# Sensor-touch.net
KiCad netlist of a schematic drawn in EAGLE
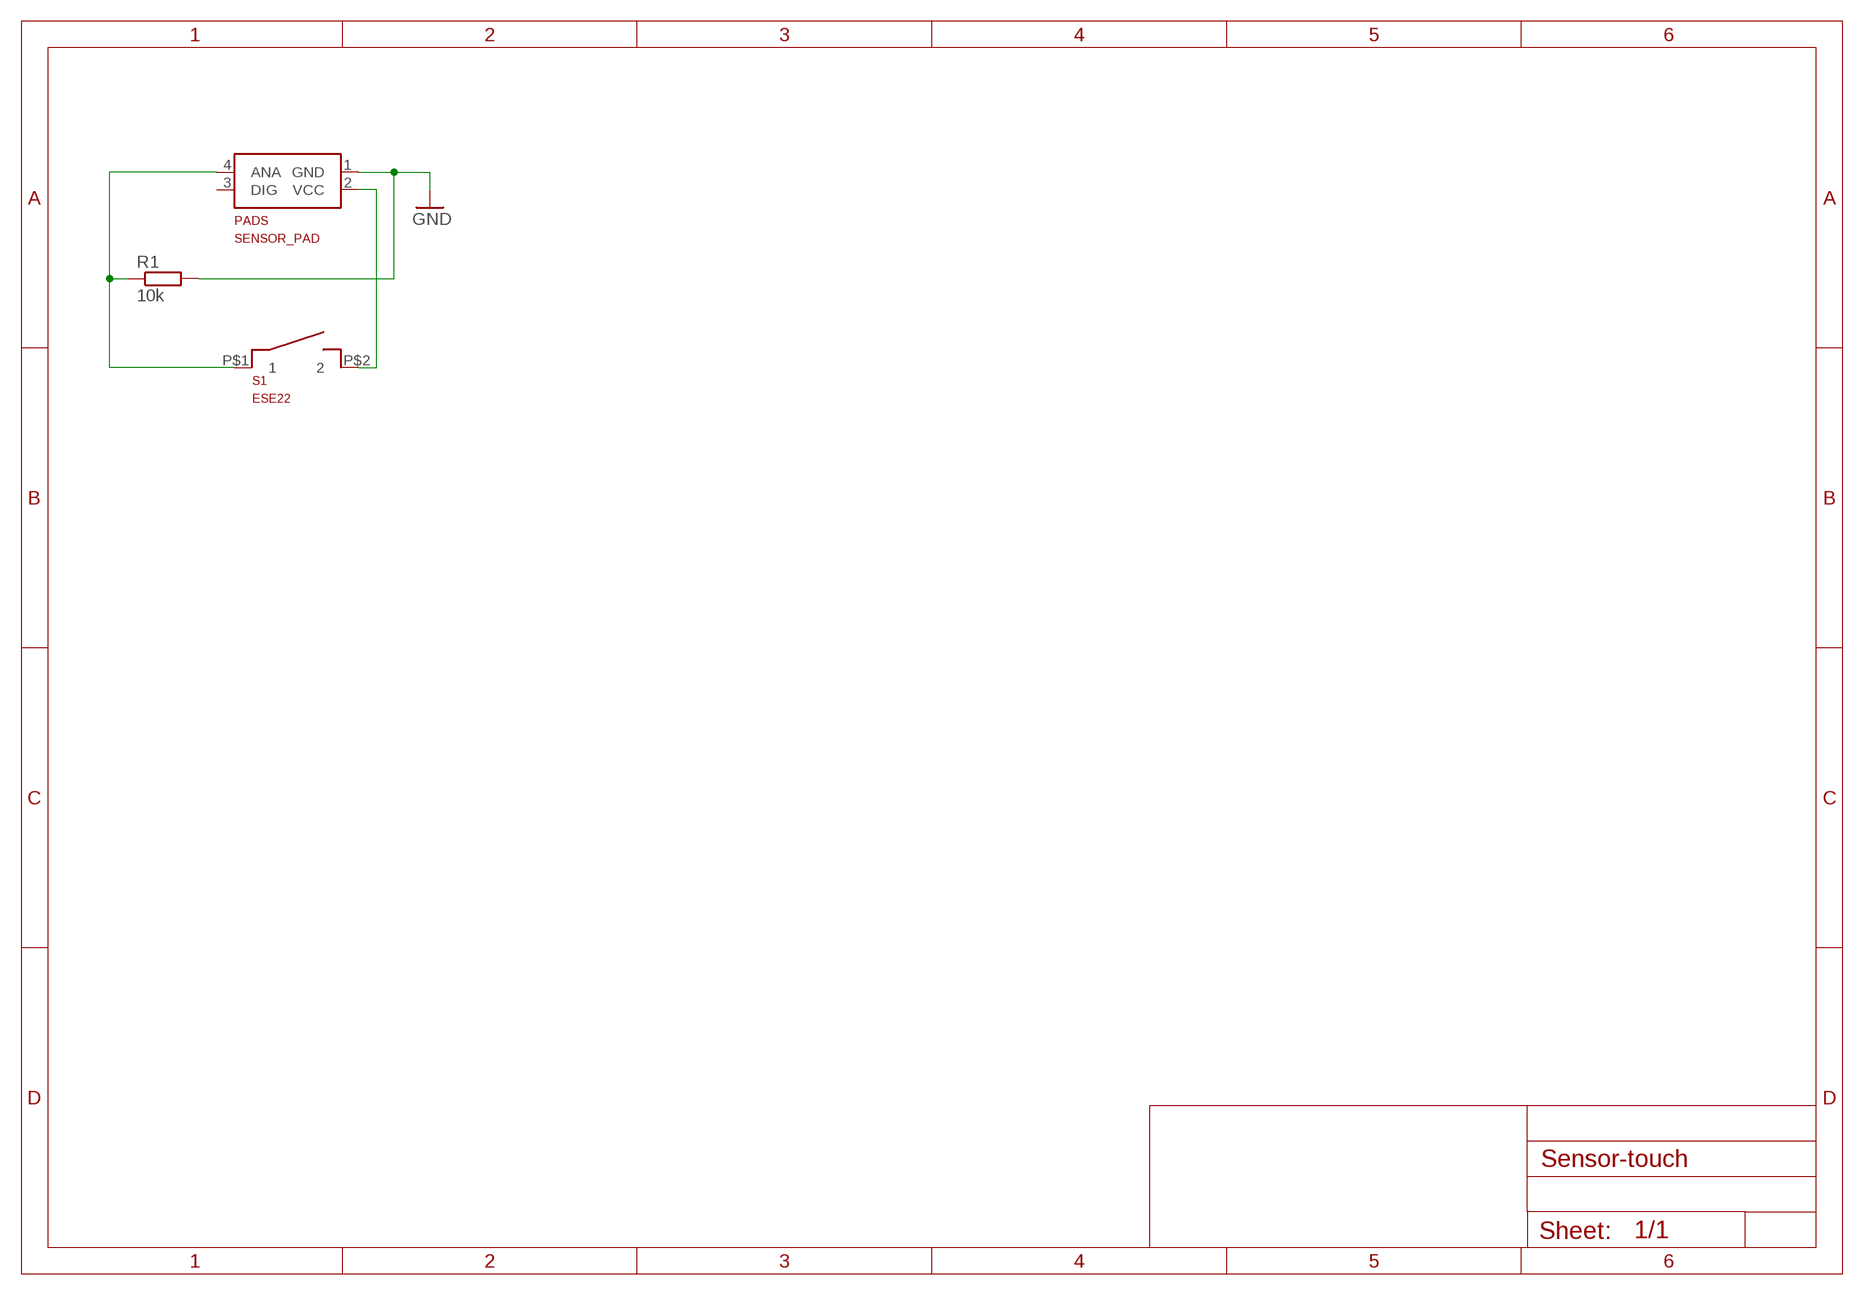
[diagram p0: schematic, sheet 1]

(export (version "E")
  (design (tool "Eeschema 10.0.6"))
  (components
    (comp (ref "PADS")
      (value "SENSOR_PAD")
      (footprint "eagle-import:SENSOR_PAD")
      (libsource (lib "eagle-import") (part "SENSOR_PAD"))
    )
    (comp (ref "R1")
      (value "10k")
      (footprint "eagle-import:R0805")
      (fields (field (name "MF") "YAGEO (PHYCOMP)") (field (name "MPN") "RC0805FR-0710KL"))
      (libsource (lib "eagle-import") (part "R-EU_R0805"))
    )
    (comp (ref "S1")
      (value "ESE22")
      (footprint "eagle-import:ESE22")
      (fields (field (name "MF") "PANASONIC ELECTRONIC COMPONENTS") (field (name "MPN") "ESE-22MH24"))
      (libsource (lib "eagle-import") (part "ESE22"))
    )
  )
  (nets
    (net (code "1") (name "GND") (class "Default")
      (node (ref "PADS") (pin "1") (pinfunction "GND_1") (pintype "bidirectional"))
      (node (ref "R1") (pin "2") (pinfunction "2_2") (pintype "passive"))
    )
    (net (code "2") (name "Net-(PADS-ANA)") (class "Default")
      (node (ref "PADS") (pin "4") (pinfunction "ANA_4") (pintype "bidirectional"))
      (node (ref "R1") (pin "1") (pinfunction "1_1") (pintype "passive"))
      (node (ref "S1") (pin "P$1") (pinfunction "1_P$1") (pintype "bidirectional"))
    )
    (net (code "3") (name "Net-(PADS-VCC)") (class "Default")
      (node (ref "PADS") (pin "2") (pinfunction "VCC_2") (pintype "bidirectional"))
      (node (ref "S1") (pin "P$2") (pinfunction "2_P$2") (pintype "bidirectional"))
    )
    (net (code "4") (name "unconnected-(PADS-DIG-Pad3)") (class "Default")
      (node (ref "PADS") (pin "3") (pinfunction "DIG_3") (pintype "bidirectional"))
    )
  )
)
